# tft_lcd_display.net
KiCad netlist of a schematic drawn in Altium Designer
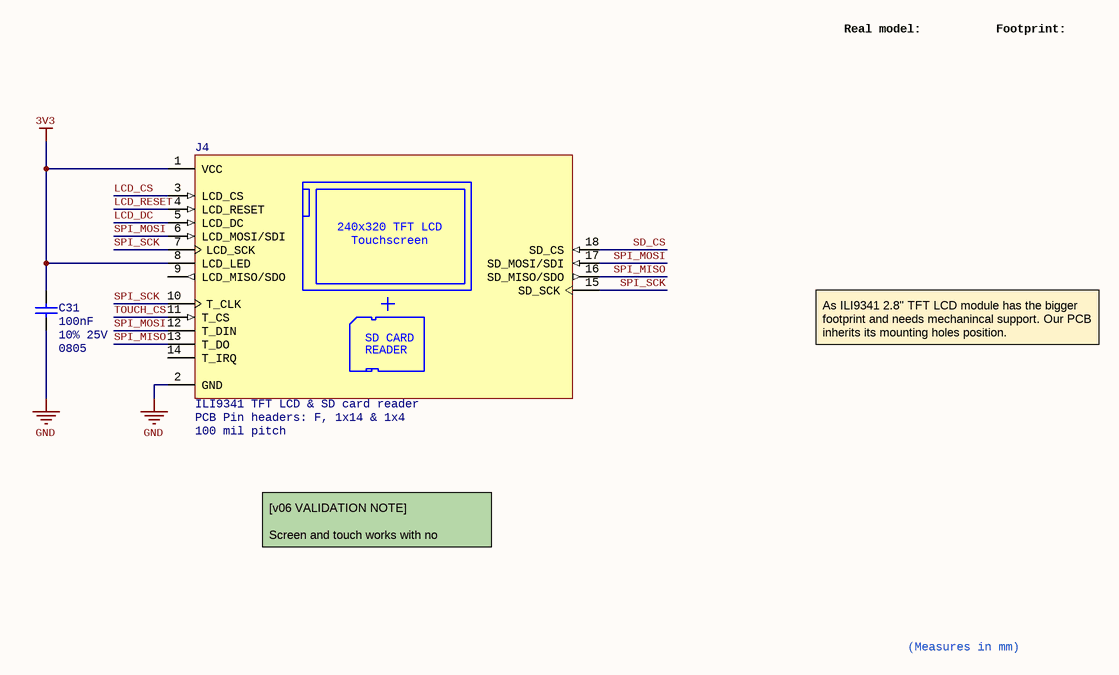
[diagram p0: tft_lcd_display.SchDoc]

(export (version "E")
  (design (tool "Eeschema 10.0.6"))
  (components
    (comp (ref "C31")
      (value "100nF")
      (footprint "CAP 0805_2012")
      (description "Ceramic cap size 0805")
      (fields
        (field (name "TOLERANCE") "10% 25V")
        (field (name "PACKAGEDESCRIPTION") "0805")
        (field (name "Comment") "Cap_cer_0805")
      )
      (libsource (lib "tik_handheld_schlib") (part "Cap_cer_0805_100nF_10%"))
    )
    (comp (ref "J4")
      (value "ILI9341 TFT LCD")
      (footprint "ILI9341 2.8\" TFT LCD + SD CARD")
      (description "ILI9341 TFT LCD Jumper pin headers., plus SD card reader pins")
      (fields
        (field (name "PART") "ILI9341 TFT LCD & SD card reader")
        (field (name "TYPE") "PCB Pin headers: F, 1x14 & 1x4")
        (field (name "PACKAGEDESCRIPTION") "100 mil pitch")
      )
      (libsource (lib "tik_handheld_schlib") (part "MOD ILI9341 TFT LCD + SD CARD READER"))
    )
  )
  (nets
    (net (code "1") (name "/LCD_CS") (class "Default")
      (node (ref "J4") (pin "3") (pinfunction "LCD_CS_3") (pintype "input"))
    )
    (net (code "2") (name "/LCD_DC") (class "Default")
      (node (ref "J4") (pin "5") (pinfunction "LCD_DC_5") (pintype "input"))
    )
    (net (code "3") (name "/LCD_RESET") (class "Default")
      (node (ref "J4") (pin "4") (pinfunction "LCD_RESET_4") (pintype "input"))
    )
    (net (code "4") (name "/SD_CS") (class "Default")
      (node (ref "J4") (pin "18") (pinfunction "SD_CS_18") (pintype "input"))
    )
    (net (code "5") (name "/SPI_MISO") (class "Default")
      (node (ref "J4") (pin "13") (pinfunction "T_DO_13") (pintype "passive"))
      (node (ref "J4") (pin "16") (pinfunction "SD_MISO/SDO_16") (pintype "output"))
    )
    (net (code "6") (name "/SPI_MOSI") (class "Default")
      (node (ref "J4") (pin "12") (pinfunction "T_DIN_12") (pintype "passive"))
      (node (ref "J4") (pin "17") (pinfunction "SD_MOSI/SDI_17") (pintype "input"))
      (node (ref "J4") (pin "6") (pinfunction "LCD_MOSI/SDI_6") (pintype "input"))
    )
    (net (code "7") (name "/SPI_SCK") (class "Default")
      (node (ref "J4") (pin "10") (pinfunction "T_CLK_10") (pintype "passive"))
      (node (ref "J4") (pin "15") (pinfunction "SD_SCK_15") (pintype "passive"))
      (node (ref "J4") (pin "7") (pinfunction "LCD_SCK_7") (pintype "passive"))
    )
    (net (code "8") (name "/TOUCH_CS") (class "Default")
      (node (ref "J4") (pin "11") (pinfunction "T_CS_11") (pintype "input"))
    )
    (net (code "9") (name "3V3") (class "Default")
      (node (ref "C31") (pin "2") (pinfunction "2_2") (pintype "passive"))
      (node (ref "J4") (pin "1") (pinfunction "VCC_1") (pintype "power_in"))
      (node (ref "J4") (pin "8") (pinfunction "LCD_LED_8") (pintype "power_in"))
    )
    (net (code "10") (name "GND") (class "Default")
      (node (ref "C31") (pin "1") (pinfunction "1_1") (pintype "passive"))
      (node (ref "J4") (pin "2") (pinfunction "GND_2") (pintype "power_in"))
    )
    (net (code "11") (name "unconnected-(J4-LCD_MISO{slash}SDO-Pad9)") (class "Default")
      (node (ref "J4") (pin "9") (pinfunction "LCD_MISO/SDO_9") (pintype "output"))
    )
    (net (code "12") (name "unconnected-(J4-T_IRQ-Pad14)") (class "Default")
      (node (ref "J4") (pin "14") (pinfunction "T_IRQ_14") (pintype "passive"))
    )
  )
)
